# 687281_099_3.net
KiCad netlist of a schematic drawn in Altium Designer
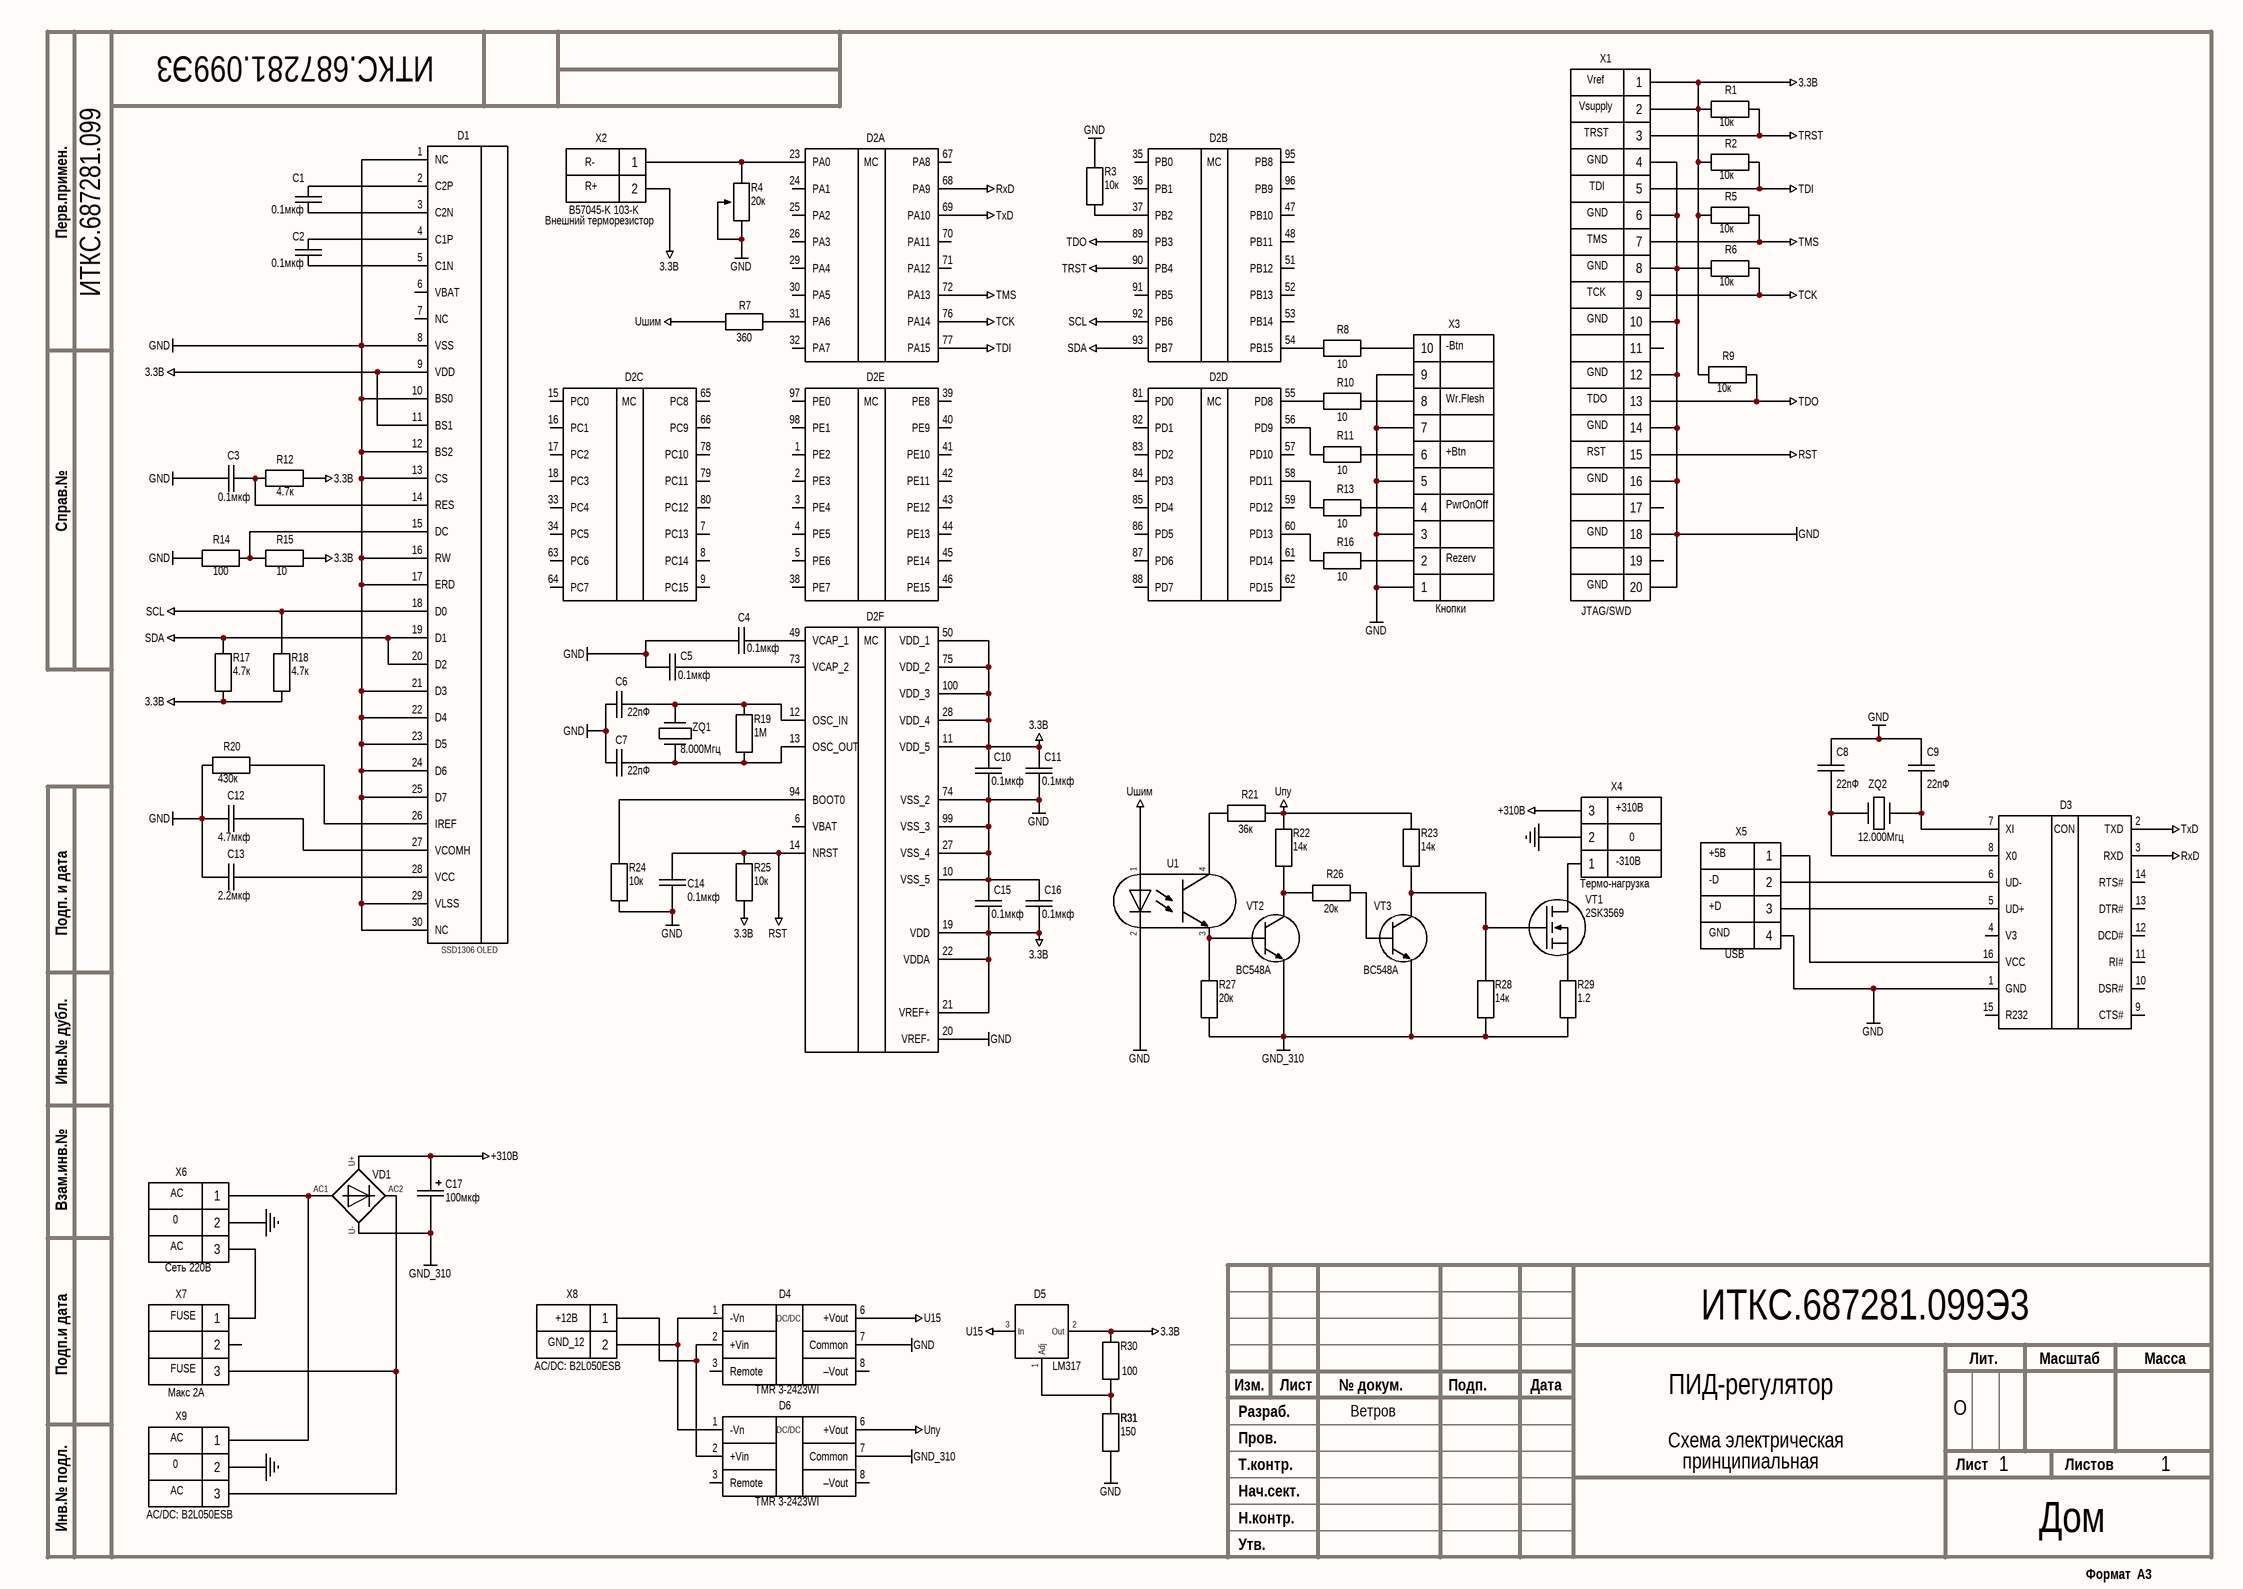
[diagram p0: ИТКС.687281.099Э3.SchDoc]

(export (version "E")
  (design (tool "Eeschema 10.0.6"))
  (components
    (comp (ref "C1")
      (value "0.1мкф")
      (footprint "C 0805")
      (description "0.1 мкФ X7R 50В 10% 0805, GRM21BR71H104KA01L")
      (libsource (lib "Passiv") (part "GRM21BR71H 104"))
    )
    (comp (ref "C2")
      (value "0.1мкф")
      (footprint "C 0805")
      (description "0.1 мкФ X7R 50В 10% 0805, GRM21BR71H104KA01L")
      (libsource (lib "Passiv") (part "GRM21BR71H 104"))
    )
    (comp (ref "C3")
      (value "0.1мкф")
      (footprint "C 0805")
      (description "0.1 мкФ X7R 50В 10% 0805, GRM21BR71H104KA01L")
      (libsource (lib "Passiv") (part "GRM21BR71H 104"))
    )
    (comp (ref "C4")
      (value "0.1мкф")
      (footprint "C 0805")
      (description "0.1 мкФ X7R 50В 10% 0805, GRM21BR71H104KA01L")
      (libsource (lib "Passiv") (part "GRM21BR71H 104"))
    )
    (comp (ref "C5")
      (value "0.1мкф")
      (footprint "C 0805")
      (description "0.1 мкФ X7R 50В 10% 0805, GRM21BR71H104KA01L")
      (libsource (lib "Passiv") (part "GRM21BR71H 104"))
    )
    (comp (ref "C6")
      (value "22пФ")
      (footprint "C 0805")
      (description "22пФ C0G 250B 5% 0805, GRM21A5C2E220J")
      (libsource (lib "Passiv") (part "GRM21A5C2E 220"))
    )
    (comp (ref "C7")
      (value "22пФ")
      (footprint "C 0805")
      (description "22пФ C0G 250B 5% 0805, GRM21A5C2E220J")
      (libsource (lib "Passiv") (part "GRM21A5C2E 220"))
    )
    (comp (ref "C8")
      (value "22пФ")
      (footprint "C 0805")
      (description "22пФ C0G 250B 5% 0805, GRM21A5C2E220J")
      (libsource (lib "Passiv") (part "GRM21A5C2E 220"))
    )
    (comp (ref "C9")
      (value "22пФ")
      (footprint "C 0805")
      (description "22пФ C0G 250B 5% 0805, GRM21A5C2E220J")
      (libsource (lib "Passiv") (part "GRM21A5C2E 220"))
    )
    (comp (ref "C10")
      (value "0.1мкф")
      (footprint "C 0805")
      (description "0.1 мкФ X7R 50В 10% 0805, GRM21BR71H104KA01L")
      (libsource (lib "Passiv") (part "GRM21BR71H 104"))
    )
    (comp (ref "C11")
      (value "0.1мкф")
      (footprint "C 0805")
      (description "0.1 мкФ X7R 50В 10% 0805, GRM21BR71H104KA01L")
      (libsource (lib "Passiv") (part "GRM21BR71H 104"))
    )
    (comp (ref "C12")
      (value "4.7мкф")
      (footprint "C 0805")
      (libsource (lib "Passiv") (part "GRM21BR61A 475"))
    )
    (comp (ref "C13")
      (value "2.2мкф")
      (footprint "C 1210")
      (description "2.2 мкФ X7R 10% 100В 1210, GRM32ER72A225K")
      (libsource (lib "Passiv") (part "GRM32ER72A 225"))
    )
    (comp (ref "C14")
      (value "0.1мкф")
      (footprint "C 0805")
      (description "0.1 мкФ X7R 50В 10% 0805, GRM21BR71H104KA01L")
      (libsource (lib "Passiv") (part "GRM21BR71H 104"))
    )
    (comp (ref "C15")
      (value "0.1мкф")
      (footprint "C 0805")
      (description "0.1 мкФ X7R 50В 10% 0805, GRM21BR71H104KA01L")
      (libsource (lib "Passiv") (part "GRM21BR71H 104"))
    )
    (comp (ref "C16")
      (value "0.1мкф")
      (footprint "C 0805")
      (description "0.1 мкФ X7R 50В 10% 0805, GRM21BR71H104KA01L")
      (libsource (lib "Passiv") (part "GRM21BR71H 104"))
    )
    (comp (ref "C17")
      (value "100мкф")
      (footprint "KSE-100")
      (description "Конденсатор электролитический KSE-100UF-400V-1830-105")
      (libsource (lib "Passiv") (part "KSE-100UF-400V-1830-105"))
    )
    (comp (ref "D1")
      (value "SSD1306 OLED")
      (footprint "50A-40BX")
      (libsource (lib "LCD") (part "SSD1306 OLED"))
    )
    (comp (ref "D2")
      (value "0")
      (footprint "LQFP - 100")
      (description "STM32F407VE6, Cortex-M3, 512k")
      (libsource (lib "") (part "STM32F407VE6_1"))
    )
    (comp (ref "D3")
      (value "CH340G")
      (footprint "SO16")
      (description "CH340G, Преобразователь интерфейса USB в UART [SOP-16]")
      (libsource (lib "CH") (part "CH340G"))
    )
    (comp (ref "D4")
      (value "TMR 3-2423WI")
      (footprint "TMR 3WI Series")
      (libsource (lib "Traco") (part "TMR 3-2423WI"))
    )
    (comp (ref "D5")
      (value "LM317")
      (footprint "TO-220")
      (description "LM317, Стабилизатор напряжения, линейный,регулируемый, 1,5А, TO220")
      (libsource (lib "LM") (part "LM317"))
    )
    (comp (ref "D6")
      (value "TMR 3-2423WI")
      (footprint "TMR 3WI Series")
      (libsource (lib "Traco") (part "TMR 3-2423WI"))
    )
    (comp (ref "R1")
      (value "10к")
      (footprint "R 0805")
      (description "0.125Вт 0805 10 кОм, 0п.1%, RT0805BRD0710KL")
      (libsource (lib "Passiv") (part "RT0805BRD07 10K"))
    )
    (comp (ref "R2")
      (value "10к")
      (footprint "R 0805")
      (description "0.125Вт 0805 10 кОм, 0п.1%, RT0805BRD0710KL")
      (libsource (lib "Passiv") (part "RT0805BRD07 10K"))
    )
    (comp (ref "R3")
      (value "10к")
      (footprint "R 0805")
      (description "0.125Вт 0805 10 кОм, 0п.1%, RT0805BRD0710KL")
      (libsource (lib "Passiv") (part "RT0805BRD07 10K"))
    )
    (comp (ref "R4")
      (value "20к")
      (footprint "JBR-3266W")
      (description "JBR-3266W-203-R, 20 кОм, Резистор подстроечный")
      (libsource (lib "Passiv") (part "JBR-3266W 203"))
    )
    (comp (ref "R5")
      (value "10к")
      (footprint "R 0805")
      (description "0.125Вт 0805 10 кОм, 0п.1%, RT0805BRD0710KL")
      (libsource (lib "Passiv") (part "RT0805BRD07 10K"))
    )
    (comp (ref "R6")
      (value "10к")
      (footprint "R 0805")
      (description "0.125Вт 0805 10 кОм, 0п.1%, RT0805BRD0710KL")
      (libsource (lib "Passiv") (part "RT0805BRD07 10K"))
    )
    (comp (ref "R7")
      (value "360")
      (footprint "R 0805")
      (description "RC0805FR-07360RL, (чип 0805 360 1%), Толстопленочный ЧИП-резистор 0805 360Ом +1% 0.125Вт")
      (libsource (lib "Passiv") (part "RC0805FR-07 360R"))
    )
    (comp (ref "R8")
      (value "10")
      (footprint "R 0805")
      (description "0.125Вт 0805 10 Ом, 1%, RC0805FR-0710RL")
      (libsource (lib "Passiv") (part "RC0805FR-07 10R"))
    )
    (comp (ref "R9")
      (value "10к")
      (footprint "R 0805")
      (description "0.125Вт 0805 10 кОм, 0п.1%, RT0805BRD0710KL")
      (libsource (lib "Passiv") (part "RT0805BRD07 10K"))
    )
    (comp (ref "R10")
      (value "10")
      (footprint "R 0805")
      (description "0.125Вт 0805 10 Ом, 1%, RC0805FR-0710RL")
      (libsource (lib "Passiv") (part "RC0805FR-07 10R"))
    )
    (comp (ref "R11")
      (value "10")
      (footprint "R 0805")
      (description "0.125Вт 0805 10 Ом, 1%, RC0805FR-0710RL")
      (libsource (lib "Passiv") (part "RC0805FR-07 10R"))
    )
    (comp (ref "R12")
      (value "4.7к")
      (footprint "R 0805")
      (description "0.125Вт 0805 4.7 кОм, 1%, RC0805FR-074K7L")
      (libsource (lib "Passiv") (part "RC0805FR07 4K7"))
    )
    (comp (ref "R13")
      (value "10")
      (footprint "R 0805")
      (description "0.125Вт 0805 10 Ом, 1%, RC0805FR-0710RL")
      (libsource (lib "Passiv") (part "RC0805FR-07 10R"))
    )
    (comp (ref "R14")
      (value "100")
      (footprint "R 0805")
      (description "0.125Вт 0805 100 Ом, 1%, RC0805FR-07100RL")
      (libsource (lib "Passiv") (part "RC0805FR-07 100R"))
    )
    (comp (ref "R15")
      (value "10")
      (footprint "R 0805")
      (description "0.125Вт 0805 10 Ом, 1%, RC0805FR-0710RL")
      (libsource (lib "") (part "RC0805FR-07 10R_1"))
    )
    (comp (ref "R16")
      (value "10")
      (footprint "R 0805")
      (description "0.125Вт 0805 10 Ом, 1%, RC0805FR-0710RL")
      (libsource (lib "Passiv") (part "RC0805FR-07 10R"))
    )
    (comp (ref "R17")
      (value "4.7к")
      (footprint "R 0805")
      (description "0.125Вт 0805 4.7 кОм, 1%, RC0805FR-074K7L")
      (libsource (lib "Passiv") (part "RC0805FR07 4K7"))
    )
    (comp (ref "R18")
      (value "4.7к")
      (footprint "R 0805")
      (description "0.125Вт 0805 4.7 кОм, 1%, RC0805FR-074K7L")
      (libsource (lib "Passiv") (part "RC0805FR07 4K7"))
    )
    (comp (ref "R19")
      (value "1М")
      (footprint "R 0805")
      (description "0.125Вт 0805 1 МОм, 1%, RC0805FR-071ML")
      (libsource (lib "Passiv") (part "RC0805FR-07 1M"))
    )
    (comp (ref "R20")
      (value "430к")
      (footprint "R 0805")
      (description "0.125Вт 0805 430 кОм, 5%, RC0805JR-07430KL")
      (libsource (lib "Passiv") (part "RC0805JR-07 430K"))
    )
    (comp (ref "R21")
      (value "36к")
      (footprint "R 0805")
      (description "RC0805FR-0736KL, (чип 0805 36.0К 1%), Толстопленочный ЧИП-резистор 0805 36кОм")
      (libsource (lib "Passiv") (part "RC0805FR-07 36K"))
    )
    (comp (ref "R22")
      (value "14к")
      (footprint "R 0805")
      (description "14 кОм 0805 1% RC0805FR-0714K")
      (libsource (lib "Passiv") (part "RC0805FR-07 14K"))
    )
    (comp (ref "R23")
      (value "14к")
      (footprint "R 0805")
      (description "14 кОм 0805 1% RC0805FR-0714K")
      (libsource (lib "Passiv") (part "RC0805FR-07 14K"))
    )
    (comp (ref "R24")
      (value "10к")
      (footprint "R 0805")
      (description "0.125Вт 0805 10 кОм, 0п.1%, RT0805BRD0710KL")
      (libsource (lib "Passiv") (part "RT0805BRD07 10K"))
    )
    (comp (ref "R25")
      (value "10к")
      (footprint "R 0805")
      (description "0.125Вт 0805 10 кОм, 0п.1%, RT0805BRD0710KL")
      (libsource (lib "Passiv") (part "RT0805BRD07 10K"))
    )
    (comp (ref "R26")
      (value "20к")
      (footprint "R 0805")
      (description "0.125Вт 0805 20 кОм, 1%, RC0805FR-0720KL")
      (libsource (lib "") (part "RC0805FR-07 20K_1"))
    )
    (comp (ref "R27")
      (value "20к")
      (footprint "R 0805")
      (description "0.125Вт 0805 20 кОм, 1%, RC0805FR-0720KL")
      (libsource (lib "Passiv") (part "RC0805FR-07 20K"))
    )
    (comp (ref "R28")
      (value "14к")
      (footprint "R 0805")
      (description "14 кОм 0805 1% RC0805FR-0714K")
      (libsource (lib "Passiv") (part "RC0805FR-07 14K"))
    )
    (comp (ref "R29")
      (value "1.2")
      (footprint "RX27-1")
      (description "RX27-1 1.2 Ом 5W 5% / SQP5, Мощный постоянный резистор , керамо-цементный корпус")
      (libsource (lib "Passiv") (part "RX27-1 1.2R"))
    )
    (comp (ref "R30")
      (value "100")
      (footprint "R 0805")
      (description "0.125Вт 0805 100 Ом, 1%, RC0805FR-07100RL")
      (libsource (lib "Passiv") (part "RC0805FR-07 100R"))
    )
    (comp (ref "R31")
      (value "150")
      (footprint "R 0805")
      (description "RC0805FR-07150RL, (чип 0805 150 1%), Толстопленочный ЧИП-резистор 0805 150Ом +1% 0.125Вт")
      (libsource (lib "Passiv") (part "RC0805FR-07 150R"))
    )
    (comp (ref "U1")
      (value "SFH618A-4X")
      (footprint "DIP4")
      (description "SFH618A-4X, Оптопара транзисторная [DIP-4]")
      (libsource (lib "Optic") (part "SFH618A-4X"))
    )
    (comp (ref "VD1")
      (value "0")
      (footprint "BR-10")
      (description "BR1001, Диодный мост однофазный 10А 100В [BR-10.] (=KBPC1001, BR101)")
      (libsource (lib "Passiv") (part "BR1001"))
    )
    (comp (ref "VT1")
      (value "2SK3569")
      (footprint "TO-220")
      (description "2SK3569, Транзистор, TT-MOSVI, N-канал, 600В, 10А")
      (libsource (lib "MOSFET") (part "2SK3569"))
    )
    (comp (ref "VT2")
      (value "BC548A")
      (footprint "TO-92")
      (description "BC548A, Транзистор NPN 30В 0.1А")
      (libsource (lib "Activ") (part "BC548A"))
    )
    (comp (ref "VT3")
      (value "BC548A")
      (footprint "TO-92")
      (description "BC548A, Транзистор NPN 30В 0.1А")
      (libsource (lib "Activ") (part "BC548A"))
    )
    (comp (ref "X1")
      (value "JTAG/SWD")
      (footprint "BH-20R (DS1013-20R) (IDC-20MR)")
      (description "BH-20R (DS1013-20R) (IDC-20MR), Вилка на плату угловая 20pin 2.54мм")
      (libsource (lib "Connectors") (part "BH-20R"))
    )
    (comp (ref "X2")
      (value "B57045-K 103-K")
      (footprint "PLS-2")
      (description "PLS-2 (DS-1021-1x2), Вилка штыревая 2.54мм 1x2pin прямая тип1")
      (libsource (lib "Connectors") (part "PLS-2"))
    )
    (comp (ref "X3")
      (value "Кнопки")
      (footprint "PLS-10")
      (description "PLS-10(DS-1021-1x10), Вилка штыревая 2.54мм 1x10pin прямая тип1")
      (libsource (lib "Connectors") (part "PLS-10"))
    )
    (comp (ref "X4")
      (value "Термо-нагрузка")
      (footprint "1-1123723-3")
      (description "1-1123723-3 (B3P-VH), Разъем 3 pin шаг 3.96мм")
      (libsource (lib "Connectors") (part "1-1123723-3"))
    )
    (comp (ref "X5")
      (value "USB")
      (footprint "PLS-4")
      (description "PLS-4 (DS-1021-1x4), Вилка штыревая 2.54мм 1x4pin прямая тип1")
      (libsource (lib "Connectors") (part "PLS-4"))
    )
    (comp (ref "X6")
      (value "Сеть 220В")
      (footprint "1-1123723-3")
      (description "1-1123723-3 (B3P-VH), Разъем 3 pin шаг 3.96мм")
      (libsource (lib "Connectors") (part "1-1123723-3"))
    )
    (comp (ref "X7")
      (value "Макс 2А")
      (footprint "1-1123723-3")
      (description "1-1123723-3 (B3P-VH), Разъем 3 pin шаг 3.96мм")
      (libsource (lib "Connectors") (part "1-1123723-3"))
    )
    (comp (ref "X8")
      (value "AC/DC: B2L050ESB")
      (footprint "PLS-2")
      (description "PLS-2 (DS-1021-1x2), Вилка штыревая 2.54мм 1x2pin прямая тип1")
      (libsource (lib "Connectors") (part "PLS-2"))
    )
    (comp (ref "X9")
      (value "AC/DC: B2L050ESB")
      (footprint "1-1123723-3")
      (description "1-1123723-3 (B3P-VH), Разъем 3 pin шаг 3.96мм")
      (libsource (lib "Connectors") (part "1-1123723-3"))
    )
    (comp (ref "ZQ1")
      (value "8.000Мгц")
      (footprint "HC-49S")
      (description "8.000Мгц, HC-49S, Кварцевый резонатор")
      (libsource (lib "Passiv") (part "HC-49S 8M"))
    )
    (comp (ref "ZQ2")
      (value "12.000Мгц")
      (footprint "HC-49S")
      (description "12.000Мгц, HC-49S, Кварцевый резонатор")
      (libsource (lib "Passiv") (part "HC-49S 12M"))
    )
  )
  (nets
    (net (code "1") (name "+310В") (class "Default")
      (node (ref "C17") (pin "1") (pinfunction "1_1") (pintype "passive"))
      (node (ref "VD1") (pin "U+") (pinfunction "U+_U+") (pintype "passive"))
      (node (ref "X4") (pin "3") (pinfunction "3_3") (pintype "passive"))
    )
    (net (code "2") (name "3.3В") (class "Default")
      (node (ref "C10") (pin "1") (pinfunction "1_1") (pintype "passive"))
      (node (ref "C11") (pin "1") (pinfunction "1_1") (pintype "passive"))
      (node (ref "C15") (pin "2") (pinfunction "2_2") (pintype "passive"))
      (node (ref "C16") (pin "2") (pinfunction "2_2") (pintype "passive"))
      (node (ref "D1") (pin "11") (pinfunction "BS1_11") (pintype "passive"))
      (node (ref "D1") (pin "9") (pinfunction "VDD_9") (pintype "passive"))
      (node (ref "D2") (pin "100") (pinfunction "VDD_3_100") (pintype "passive"))
      (node (ref "D2") (pin "11") (pinfunction "VDD_5_11") (pintype "passive"))
      (node (ref "D2") (pin "19") (pinfunction "VDD_19") (pintype "passive"))
      (node (ref "D2") (pin "21") (pinfunction "VREF+_21") (pintype "passive"))
      (node (ref "D2") (pin "22") (pinfunction "VDDA_22") (pintype "passive"))
      (node (ref "D2") (pin "28") (pinfunction "VDD_4_28") (pintype "passive"))
      (node (ref "D2") (pin "50") (pinfunction "VDD_1_50") (pintype "passive"))
      (node (ref "D2") (pin "75") (pinfunction "VDD_2_75") (pintype "passive"))
      (node (ref "D5") (pin "2") (pinfunction "Out_2") (pintype "passive"))
      (node (ref "R1") (pin "1") (pinfunction "1_1") (pintype "passive"))
      (node (ref "R12") (pin "2") (pinfunction "2_2") (pintype "passive"))
      (node (ref "R15") (pin "2") (pinfunction "2_2") (pintype "passive"))
      (node (ref "R17") (pin "1") (pinfunction "1_1") (pintype "passive"))
      (node (ref "R18") (pin "1") (pinfunction "1_1") (pintype "passive"))
      (node (ref "R2") (pin "1") (pinfunction "1_1") (pintype "passive"))
      (node (ref "R25") (pin "1") (pinfunction "1_1") (pintype "passive"))
      (node (ref "R30") (pin "2") (pinfunction "2_2") (pintype "passive"))
      (node (ref "R5") (pin "1") (pinfunction "1_1") (pintype "passive"))
      (node (ref "R9") (pin "1") (pinfunction "1_1") (pintype "passive"))
      (node (ref "X1") (pin "1") (pinfunction "1_1") (pintype "passive"))
      (node (ref "X1") (pin "2") (pinfunction "2_2") (pintype "passive"))
      (node (ref "X2") (pin "2") (pinfunction "2_2") (pintype "passive"))
    )
    (net (code "3") (name "GND") (class "Default")
      (node (ref "C10") (pin "2") (pinfunction "2_2") (pintype "passive"))
      (node (ref "C11") (pin "2") (pinfunction "2_2") (pintype "passive"))
      (node (ref "C12") (pin "1") (pinfunction "1_1") (pintype "passive"))
      (node (ref "C13") (pin "1") (pinfunction "1_1") (pintype "passive"))
      (node (ref "C14") (pin "2") (pinfunction "2_2") (pintype "passive"))
      (node (ref "C15") (pin "1") (pinfunction "1_1") (pintype "passive"))
      (node (ref "C16") (pin "1") (pinfunction "1_1") (pintype "passive"))
      (node (ref "C3") (pin "2") (pinfunction "2_2") (pintype "passive"))
      (node (ref "C4") (pin "2") (pinfunction "2_2") (pintype "passive"))
      (node (ref "C5") (pin "2") (pinfunction "2_2") (pintype "passive"))
      (node (ref "C6") (pin "1") (pinfunction "1_1") (pintype "passive"))
      (node (ref "C7") (pin "1") (pinfunction "1_1") (pintype "passive"))
      (node (ref "C8") (pin "2") (pinfunction "2_2") (pintype "passive"))
      (node (ref "C9") (pin "2") (pinfunction "2_2") (pintype "passive"))
      (node (ref "D1") (pin "1") (pinfunction "NC_1") (pintype "passive"))
      (node (ref "D1") (pin "10") (pinfunction "BS0_10") (pintype "passive"))
      (node (ref "D1") (pin "12") (pinfunction "BS2_12") (pintype "passive"))
      (node (ref "D1") (pin "13") (pinfunction "CS_13") (pintype "passive"))
      (node (ref "D1") (pin "16") (pinfunction "RW_16") (pintype "passive"))
      (node (ref "D1") (pin "17") (pinfunction "ERD_17") (pintype "passive"))
      (node (ref "D1") (pin "21") (pinfunction "D3_21") (pintype "passive"))
      (node (ref "D1") (pin "22") (pinfunction "D4_22") (pintype "passive"))
      (node (ref "D1") (pin "23") (pinfunction "D5_23") (pintype "passive"))
      (node (ref "D1") (pin "24") (pinfunction "D6_24") (pintype "passive"))
      (node (ref "D1") (pin "25") (pinfunction "D7_25") (pintype "passive"))
      (node (ref "D1") (pin "29") (pinfunction "VLSS_29") (pintype "passive"))
      (node (ref "D1") (pin "30") (pinfunction "NC_30") (pintype "passive"))
      (node (ref "D1") (pin "8") (pinfunction "VSS_8") (pintype "passive"))
      (node (ref "D2") (pin "10") (pinfunction "VSS_5_10") (pintype "passive"))
      (node (ref "D2") (pin "20") (pinfunction "VREF-_20") (pintype "passive"))
      (node (ref "D2") (pin "27") (pinfunction "VSS_4_27") (pintype "passive"))
      (node (ref "D2") (pin "74") (pinfunction "VSS_2_74") (pintype "passive"))
      (node (ref "D2") (pin "99") (pinfunction "VSS_3_99") (pintype "passive"))
      (node (ref "D3") (pin "1") (pinfunction "GND_1") (pintype "passive"))
      (node (ref "D4") (pin "7") (pinfunction "Common_7") (pintype "passive"))
      (node (ref "R14") (pin "1") (pinfunction "1_1") (pintype "passive"))
      (node (ref "R20") (pin "1") (pinfunction "1_1") (pintype "passive"))
      (node (ref "R24") (pin "1") (pinfunction "1_1") (pintype "passive"))
      (node (ref "R3") (pin "2") (pinfunction "2_2") (pintype "passive"))
      (node (ref "R31") (pin "1") (pinfunction "1_1") (pintype "passive"))
      (node (ref "R4") (pin "1") (pinfunction "1_1") (pintype "passive"))
      (node (ref "R4") (pin "3") (pinfunction "3_3") (pintype "passive"))
      (node (ref "R6") (pin "1") (pinfunction "1_1") (pintype "passive"))
      (node (ref "U1") (pin "2") (pinfunction "C_2") (pintype "passive"))
      (node (ref "X1") (pin "10") (pinfunction "10_10") (pintype "passive"))
      (node (ref "X1") (pin "12") (pinfunction "12_12") (pintype "passive"))
      (node (ref "X1") (pin "14") (pinfunction "14_14") (pintype "passive"))
      (node (ref "X1") (pin "16") (pinfunction "16_16") (pintype "passive"))
      (node (ref "X1") (pin "18") (pinfunction "18_18") (pintype "passive"))
      (node (ref "X1") (pin "20") (pinfunction "20_20") (pintype "passive"))
      (node (ref "X1") (pin "4") (pinfunction "4_4") (pintype "passive"))
      (node (ref "X1") (pin "6") (pinfunction "6_6") (pintype "passive"))
      (node (ref "X1") (pin "8") (pinfunction "8_8") (pintype "passive"))
      (node (ref "X3") (pin "1") (pinfunction "1_1") (pintype "passive"))
      (node (ref "X3") (pin "3") (pinfunction "3_3") (pintype "passive"))
      (node (ref "X3") (pin "5") (pinfunction "5_5") (pintype "passive"))
      (node (ref "X3") (pin "7") (pinfunction "7_7") (pintype "passive"))
      (node (ref "X3") (pin "9") (pinfunction "9_9") (pintype "passive"))
      (node (ref "X5") (pin "4") (pinfunction "4_4") (pintype "passive"))
    )
    (net (code "4") (name "GND_310") (class "Default")
      (node (ref "C17") (pin "2") (pinfunction "2_2") (pintype "passive"))
      (node (ref "D6") (pin "7") (pinfunction "Common_7") (pintype "passive"))
      (node (ref "R27") (pin "1") (pinfunction "1_1") (pintype "passive"))
      (node (ref "R28") (pin "1") (pinfunction "1_1") (pintype "passive"))
      (node (ref "R29") (pin "1") (pinfunction "1_1") (pintype "passive"))
      (node (ref "VD1") (pin "U-") (pinfunction "U-_U-") (pintype "passive"))
      (node (ref "VT2") (pin "E") (pinfunction "E_E") (pintype "passive"))
      (node (ref "VT3") (pin "E") (pinfunction "E_E") (pintype "passive"))
    )
    (net (code "5") (name "GND_set") (class "Default")
      (node (ref "X4") (pin "2") (pinfunction "2_2") (pintype "passive"))
      (node (ref "X6") (pin "2") (pinfunction "2_2") (pintype "passive"))
      (node (ref "X9") (pin "2") (pinfunction "2_2") (pintype "passive"))
    )
    (net (code "6") (name "Net-(D1-C1N)") (class "Default")
      (node (ref "C2") (pin "1") (pinfunction "1_1") (pintype "passive"))
      (node (ref "D1") (pin "5") (pinfunction "C1N_5") (pintype "passive"))
    )
    (net (code "7") (name "Net-(D1-C1P)") (class "Default")
      (node (ref "C2") (pin "2") (pinfunction "2_2") (pintype "passive"))
      (node (ref "D1") (pin "4") (pinfunction "C1P_4") (pintype "passive"))
    )
    (net (code "8") (name "Net-(D1-C2N)") (class "Default")
      (node (ref "C1") (pin "1") (pinfunction "1_1") (pintype "passive"))
      (node (ref "D1") (pin "3") (pinfunction "C2N_3") (pintype "passive"))
    )
    (net (code "9") (name "Net-(D1-C2P)") (class "Default")
      (node (ref "C1") (pin "2") (pinfunction "2_2") (pintype "passive"))
      (node (ref "D1") (pin "2") (pinfunction "C2P_2") (pintype "passive"))
    )
    (net (code "10") (name "Net-(D1-DC)") (class "Default")
      (node (ref "D1") (pin "15") (pinfunction "DC_15") (pintype "passive"))
      (node (ref "R14") (pin "2") (pinfunction "2_2") (pintype "passive"))
      (node (ref "R15") (pin "1") (pinfunction "1_1") (pintype "passive"))
    )
    (net (code "11") (name "Net-(D1-IREF)") (class "Default")
      (node (ref "D1") (pin "26") (pinfunction "IREF_26") (pintype "passive"))
      (node (ref "R20") (pin "2") (pinfunction "2_2") (pintype "passive"))
    )
    (net (code "12") (name "Net-(D1-RES)") (class "Default")
      (node (ref "C3") (pin "1") (pinfunction "1_1") (pintype "passive"))
      (node (ref "D1") (pin "14") (pinfunction "RES_14") (pintype "passive"))
      (node (ref "R12") (pin "1") (pinfunction "1_1") (pintype "passive"))
    )
    (net (code "13") (name "Net-(D1-VCC)") (class "Default")
      (node (ref "C13") (pin "2") (pinfunction "2_2") (pintype "passive"))
      (node (ref "D1") (pin "28") (pinfunction "VCC_28") (pintype "passive"))
    )
    (net (code "14") (name "Net-(D1-VCOMH)") (class "Default")
      (node (ref "C12") (pin "2") (pinfunction "2_2") (pintype "passive"))
      (node (ref "D1") (pin "27") (pinfunction "VCOMH_27") (pintype "passive"))
    )
    (net (code "15") (name "Net-(D2A-PA0)") (class "Default")
      (node (ref "D2") (pin "23") (pinfunction "PA0_23") (pintype "passive"))
      (node (ref "R4") (pin "2") (pinfunction "2_2") (pintype "passive"))
      (node (ref "X2") (pin "1") (pinfunction "1_1") (pintype "passive"))
    )
    (net (code "16") (name "Net-(D2A-PA6)") (class "Default")
      (node (ref "D2") (pin "31") (pinfunction "PA6_31") (pintype "passive"))
      (node (ref "R7") (pin "1") (pinfunction "1_1") (pintype "passive"))
    )
    (net (code "17") (name "Net-(D2B-PB2)") (class "Default")
      (node (ref "D2") (pin "37") (pinfunction "PB2_37") (pintype "passive"))
      (node (ref "R3") (pin "1") (pinfunction "1_1") (pintype "passive"))
    )
    (net (code "18") (name "Net-(D2B-PB15)") (class "Default")
      (node (ref "D2") (pin "54") (pinfunction "PB15_54") (pintype "passive"))
      (node (ref "R8") (pin "1") (pinfunction "1_1") (pintype "passive"))
    )
    (net (code "19") (name "Net-(D2D-PD8)") (class "Default")
      (node (ref "D2") (pin "55") (pinfunction "PD8_55") (pintype "passive"))
      (node (ref "R10") (pin "1") (pinfunction "1_1") (pintype "passive"))
    )
    (net (code "20") (name "Net-(D2D-PD9)") (class "Default")
      (node (ref "D2") (pin "56") (pinfunction "PD9_56") (pintype "passive"))
      (node (ref "R11") (pin "1") (pinfunction "1_1") (pintype "passive"))
    )
    (net (code "21") (name "Net-(D2D-PD11)") (class "Default")
      (node (ref "D2") (pin "58") (pinfunction "PD11_58") (pintype "passive"))
      (node (ref "R13") (pin "1") (pinfunction "1_1") (pintype "passive"))
    )
    (net (code "22") (name "Net-(D2D-PD13)") (class "Default")
      (node (ref "D2") (pin "60") (pinfunction "PD13_60") (pintype "passive"))
      (node (ref "R16") (pin "1") (pinfunction "1_1") (pintype "passive"))
    )
    (net (code "23") (name "Net-(D2F-BOOT0)") (class "Default")
      (node (ref "D2") (pin "94") (pinfunction "BOOT0_94") (pintype "passive"))
      (node (ref "R24") (pin "2") (pinfunction "2_2") (pintype "passive"))
    )
    (net (code "24") (name "Net-(D2F-OSC_IN)") (class "Default")
      (node (ref "C6") (pin "2") (pinfunction "2_2") (pintype "passive"))
      (node (ref "D2") (pin "12") (pinfunction "OSC_IN_12") (pintype "passive"))
      (node (ref "R19") (pin "2") (pinfunction "2_2") (pintype "passive"))
      (node (ref "ZQ1") (pin "2") (pinfunction "2_2") (pintype "passive"))
    )
    (net (code "25") (name "Net-(D2F-OSC_OUT)") (class "Default")
      (node (ref "C7") (pin "2") (pinfunction "2_2") (pintype "passive"))
      (node (ref "D2") (pin "13") (pinfunction "OSC_OUT_13") (pintype "passive"))
      (node (ref "R19") (pin "1") (pinfunction "1_1") (pintype "passive"))
      (node (ref "ZQ1") (pin "1") (pinfunction "1_1") (pintype "passive"))
    )
    (net (code "26") (name "Net-(D2F-VCAP_1)") (class "Default")
      (node (ref "C4") (pin "1") (pinfunction "1_1") (pintype "passive"))
      (node (ref "D2") (pin "49") (pinfunction "VCAP_1_49") (pintype "passive"))
    )
    (net (code "27") (name "Net-(D2F-VCAP_2)") (class "Default")
      (node (ref "C5") (pin "1") (pinfunction "1_1") (pintype "passive"))
      (node (ref "D2") (pin "73") (pinfunction "VCAP_2_73") (pintype "passive"))
    )
    (net (code "28") (name "Net-(D3-UD+)") (class "Default")
      (node (ref "D3") (pin "5") (pinfunction "UD+_5") (pintype "passive"))
      (node (ref "X5") (pin "3") (pinfunction "3_3") (pintype "passive"))
    )
    (net (code "29") (name "Net-(D3-UD-)") (class "Default")
      (node (ref "D3") (pin "6") (pinfunction "UD-_6") (pintype "passive"))
      (node (ref "X5") (pin "2") (pinfunction "2_2") (pintype "passive"))
    )
    (net (code "30") (name "Net-(D3-VCC)") (class "Default")
      (node (ref "D3") (pin "16") (pinfunction "VCC_16") (pintype "passive"))
      (node (ref "X5") (pin "1") (pinfunction "1_1") (pintype "passive"))
    )
    (net (code "31") (name "Net-(D3-X0)") (class "Default")
      (node (ref "C8") (pin "1") (pinfunction "1_1") (pintype "passive"))
      (node (ref "D3") (pin "8") (pinfunction "X0_8") (pintype "passive"))
      (node (ref "ZQ2") (pin "1") (pinfunction "1_1") (pintype "passive"))
    )
    (net (code "32") (name "Net-(D3-XI)") (class "Default")
      (node (ref "C9") (pin "1") (pinfunction "1_1") (pintype "passive"))
      (node (ref "D3") (pin "7") (pinfunction "XI_7") (pintype "passive"))
      (node (ref "ZQ2") (pin "2") (pinfunction "2_2") (pintype "passive"))
    )
    (net (code "33") (name "Net-(D4-+Vin)") (class "Default")
      (node (ref "D4") (pin "2") (pinfunction "+Vin_2") (pintype "passive"))
      (node (ref "D6") (pin "2") (pinfunction "+Vin_2") (pintype "passive"))
      (node (ref "X8") (pin "1") (pinfunction "1_1") (pintype "passive"))
    )
    (net (code "34") (name "Net-(D4--Vn)") (class "Default")
      (node (ref "D4") (pin "1") (pinfunction "-Vn_1") (pintype "passive"))
      (node (ref "D6") (pin "1") (pinfunction "-Vn_1") (pintype "passive"))
      (node (ref "X8") (pin "2") (pinfunction "2_2") (pintype "passive"))
    )
    (net (code "35") (name "Net-(D5-Adj)") (class "Default")
      (node (ref "D5") (pin "1") (pinfunction "Adj_1") (pintype "passive"))
      (node (ref "R30") (pin "1") (pinfunction "1_1") (pintype "passive"))
      (node (ref "R31") (pin "2") (pinfunction "2_2") (pintype "passive"))
    )
    (net (code "36") (name "Net-(R8-Pad2)") (class "Default")
      (node (ref "R8") (pin "2") (pinfunction "2_2") (pintype "passive"))
      (node (ref "X3") (pin "10") (pinfunction "10_10") (pintype "passive"))
    )
    (net (code "37") (name "Net-(R10-Pad2)") (class "Default")
      (node (ref "R10") (pin "2") (pinfunction "2_2") (pintype "passive"))
      (node (ref "X3") (pin "8") (pinfunction "8_8") (pintype "passive"))
    )
    (net (code "38") (name "Net-(R11-Pad2)") (class "Default")
      (node (ref "R11") (pin "2") (pinfunction "2_2") (pintype "passive"))
      (node (ref "X3") (pin "6") (pinfunction "6_6") (pintype "passive"))
    )
    (net (code "39") (name "Net-(R13-Pad2)") (class "Default")
      (node (ref "R13") (pin "2") (pinfunction "2_2") (pintype "passive"))
      (node (ref "X3") (pin "4") (pinfunction "4_4") (pintype "passive"))
    )
    (net (code "40") (name "Net-(R16-Pad2)") (class "Default")
      (node (ref "R16") (pin "2") (pinfunction "2_2") (pintype "passive"))
      (node (ref "X3") (pin "2") (pinfunction "2_2") (pintype "passive"))
    )
    (net (code "41") (name "Net-(R21-Pad1)") (class "Default")
      (node (ref "R21") (pin "1") (pinfunction "1_1") (pintype "passive"))
      (node (ref "U1") (pin "4") (pinfunction "C_4") (pintype "passive"))
    )
    (net (code "42") (name "Net-(R22-Pad1)") (class "Default")
      (node (ref "R22") (pin "1") (pinfunction "1_1") (pintype "passive"))
      (node (ref "R26") (pin "2") (pinfunction "2_2") (pintype "passive"))
      (node (ref "VT2") (pin "K") (pinfunction "K_K") (pintype "passive"))
    )
    (net (code "43") (name "Net-(R26-Pad1)") (class "Default")
      (node (ref "R26") (pin "1") (pinfunction "1_1") (pintype "passive"))
      (node (ref "VT3") (pin "B") (pinfunction "B_B") (pintype "passive"))
    )
    (net (code "44") (name "Net-(U1-E)") (class "Default")
      (node (ref "R27") (pin "2") (pinfunction "2_2") (pintype "passive"))
      (node (ref "U1") (pin "3") (pinfunction "E_3") (pintype "passive"))
      (node (ref "VT2") (pin "B") (pinfunction "B_B") (pintype "passive"))
    )
    (net (code "45") (name "Net-(VD1-PadAC1)") (class "Default")
      (node (ref "VD1") (pin "AC1") (pinfunction "AC1_AC1") (pintype "passive"))
      (node (ref "X6") (pin "1") (pinfunction "1_1") (pintype "passive"))
      (node (ref "X9") (pin "1") (pinfunction "1_1") (pintype "passive"))
    )
    (net (code "46") (name "Net-(VD1-PadAC2)") (class "Default")
      (node (ref "VD1") (pin "AC2") (pinfunction "AC2_AC2") (pintype "passive"))
      (node (ref "X7") (pin "3") (pinfunction "3_3") (pintype "passive"))
      (node (ref "X9") (pin "3") (pinfunction "3_3") (pintype "passive"))
    )
    (net (code "47") (name "Net-(VT1-Drain)") (class "Default")
      (node (ref "VT1") (pin "2") (pinfunction "Drain_2") (pintype "passive"))
      (node (ref "X4") (pin "1") (pinfunction "1_1") (pintype "passive"))
    )
    (net (code "48") (name "Net-(VT1-Gate)") (class "Default")
      (node (ref "R23") (pin "1") (pinfunction "1_1") (pintype "passive"))
      (node (ref "R28") (pin "2") (pinfunction "2_2") (pintype "passive"))
      (node (ref "VT1") (pin "1") (pinfunction "Gate_1") (pintype "passive"))
      (node (ref "VT3") (pin "K") (pinfunction "K_K") (pintype "passive"))
    )
    (net (code "49") (name "Net-(VT1-Source)") (class "Default")
      (node (ref "R29") (pin "2") (pinfunction "2_2") (pintype "passive"))
      (node (ref "VT1") (pin "3") (pinfunction "Source_3") (pintype "passive"))
    )
    (net (code "50") (name "Net-(X6-Pad3)") (class "Default")
      (node (ref "X6") (pin "3") (pinfunction "3_3") (pintype "passive"))
      (node (ref "X7") (pin "1") (pinfunction "1_1") (pintype "passive"))
    )
    (net (code "51") (name "RST") (class "Default")
      (node (ref "C14") (pin "1") (pinfunction "1_1") (pintype "passive"))
      (node (ref "D2") (pin "14") (pinfunction "NRST_14") (pintype "passive"))
      (node (ref "R25") (pin "2") (pinfunction "2_2") (pintype "passive"))
      (node (ref "X1") (pin "15") (pinfunction "15_15") (pintype "passive"))
    )
    (net (code "52") (name "RxD") (class "Default")
      (node (ref "D2") (pin "68") (pinfunction "PA9_68") (pintype "passive"))
      (node (ref "D3") (pin "3") (pinfunction "RXD_3") (pintype "passive"))
    )
    (net (code "53") (name "SCL") (class "Default")
      (node (ref "D1") (pin "18") (pinfunction "D0_18") (pintype "passive"))
      (node (ref "D2") (pin "92") (pinfunction "PB6_92") (pintype "passive"))
      (node (ref "R18") (pin "2") (pinfunction "2_2") (pintype "passive"))
    )
    (net (code "54") (name "SDA") (class "Default")
      (node (ref "D1") (pin "19") (pinfunction "D1_19") (pintype "passive"))
      (node (ref "D1") (pin "20") (pinfunction "D2_20") (pintype "passive"))
      (node (ref "D2") (pin "93") (pinfunction "PB7_93") (pintype "passive"))
      (node (ref "R17") (pin "2") (pinfunction "2_2") (pintype "passive"))
    )
    (net (code "55") (name "TCK") (class "Default")
      (node (ref "D2") (pin "76") (pinfunction "PA14_76") (pintype "passive"))
      (node (ref "R6") (pin "2") (pinfunction "2_2") (pintype "passive"))
      (node (ref "X1") (pin "9") (pinfunction "9_9") (pintype "passive"))
    )
    (net (code "56") (name "TDI") (class "Default")
      (node (ref "D2") (pin "77") (pinfunction "PA15_77") (pintype "passive"))
      (node (ref "R2") (pin "2") (pinfunction "2_2") (pintype "passive"))
      (node (ref "X1") (pin "5") (pinfunction "5_5") (pintype "passive"))
    )
    (net (code "57") (name "TDO") (class "Default")
      (node (ref "D2") (pin "89") (pinfunction "PB3_89") (pintype "passive"))
      (node (ref "R9") (pin "2") (pinfunction "2_2") (pintype "passive"))
      (node (ref "X1") (pin "13") (pinfunction "13_13") (pintype "passive"))
    )
    (net (code "58") (name "TMS") (class "Default")
      (node (ref "D2") (pin "72") (pinfunction "PA13_72") (pintype "passive"))
      (node (ref "R5") (pin "2") (pinfunction "2_2") (pintype "passive"))
      (node (ref "X1") (pin "7") (pinfunction "7_7") (pintype "passive"))
    )
    (net (code "59") (name "TRST") (class "Default")
      (node (ref "D2") (pin "90") (pinfunction "PB4_90") (pintype "passive"))
      (node (ref "R1") (pin "2") (pinfunction "2_2") (pintype "passive"))
      (node (ref "X1") (pin "3") (pinfunction "3_3") (pintype "passive"))
    )
    (net (code "60") (name "TxD") (class "Default")
      (node (ref "D2") (pin "69") (pinfunction "PA10_69") (pintype "passive"))
      (node (ref "D3") (pin "2") (pinfunction "TXD_2") (pintype "passive"))
    )
    (net (code "61") (name "U15") (class "Default")
      (node (ref "D4") (pin "6") (pinfunction "+Vout_6") (pintype "passive"))
      (node (ref "D5") (pin "3") (pinfunction "In_3") (pintype "passive"))
    )
    (net (code "62") (name "Uпу") (class "Default")
      (node (ref "D6") (pin "6") (pinfunction "+Vout_6") (pintype "passive"))
      (node (ref "R21") (pin "2") (pinfunction "2_2") (pintype "passive"))
      (node (ref "R22") (pin "2") (pinfunction "2_2") (pintype "passive"))
      (node (ref "R23") (pin "2") (pinfunction "2_2") (pintype "passive"))
    )
    (net (code "63") (name "Uшим") (class "Default")
      (node (ref "R7") (pin "2") (pinfunction "2_2") (pintype "passive"))
      (node (ref "U1") (pin "1") (pinfunction "A_1") (pintype "passive"))
    )
    (net (code "64") (name "unconnected-(D1-NC-Pad7)") (class "Default")
      (node (ref "D1") (pin "7") (pinfunction "NC_7") (pintype "passive"))
    )
    (net (code "65") (name "unconnected-(D1-VBAT-Pad6)") (class "Default")
      (node (ref "D1") (pin "6") (pinfunction "VBAT_6") (pintype "passive"))
    )
    (net (code "66") (name "unconnected-(D2A-PA1-Pad24)") (class "Default")
      (node (ref "D2") (pin "24") (pinfunction "PA1_24") (pintype "passive"))
    )
    (net (code "67") (name "unconnected-(D2A-PA2-Pad25)") (class "Default")
      (node (ref "D2") (pin "25") (pinfunction "PA2_25") (pintype "passive"))
    )
    (net (code "68") (name "unconnected-(D2A-PA3-Pad26)") (class "Default")
      (node (ref "D2") (pin "26") (pinfunction "PA3_26") (pintype "passive"))
    )
    (net (code "69") (name "unconnected-(D2A-PA4-Pad29)") (class "Default")
      (node (ref "D2") (pin "29") (pinfunction "PA4_29") (pintype "passive"))
    )
    (net (code "70") (name "unconnected-(D2A-PA5-Pad30)") (class "Default")
      (node (ref "D2") (pin "30") (pinfunction "PA5_30") (pintype "passive"))
    )
    (net (code "71") (name "unconnected-(D2A-PA7-Pad32)") (class "Default")
      (node (ref "D2") (pin "32") (pinfunction "PA7_32") (pintype "passive"))
    )
    (net (code "72") (name "unconnected-(D2A-PA8-Pad67)") (class "Default")
      (node (ref "D2") (pin "67") (pinfunction "PA8_67") (pintype "passive"))
    )
    (net (code "73") (name "unconnected-(D2A-PA11-Pad70)") (class "Default")
      (node (ref "D2") (pin "70") (pinfunction "PA11_70") (pintype "passive"))
    )
    (net (code "74") (name "unconnected-(D2A-PA12-Pad71)") (class "Default")
      (node (ref "D2") (pin "71") (pinfunction "PA12_71") (pintype "passive"))
    )
    (net (code "75") (name "unconnected-(D2B-PB0-Pad35)") (class "Default")
      (node (ref "D2") (pin "35") (pinfunction "PB0_35") (pintype "passive"))
    )
    (net (code "76") (name "unconnected-(D2B-PB1-Pad36)") (class "Default")
      (node (ref "D2") (pin "36") (pinfunction "PB1_36") (pintype "passive"))
    )
    (net (code "77") (name "unconnected-(D2B-PB5-Pad91)") (class "Default")
      (node (ref "D2") (pin "91") (pinfunction "PB5_91") (pintype "passive"))
    )
    (net (code "78") (name "unconnected-(D2B-PB8-Pad95)") (class "Default")
      (node (ref "D2") (pin "95") (pinfunction "PB8_95") (pintype "passive"))
    )
    (net (code "79") (name "unconnected-(D2B-PB9-Pad96)") (class "Default")
      (node (ref "D2") (pin "96") (pinfunction "PB9_96") (pintype "passive"))
    )
    (net (code "80") (name "unconnected-(D2B-PB10-Pad47)") (class "Default")
      (node (ref "D2") (pin "47") (pinfunction "PB10_47") (pintype "passive"))
    )
    (net (code "81") (name "unconnected-(D2B-PB11-Pad48)") (class "Default")
      (node (ref "D2") (pin "48") (pinfunction "PB11_48") (pintype "passive"))
    )
    (net (code "82") (name "unconnected-(D2B-PB12-Pad51)") (class "Default")
      (node (ref "D2") (pin "51") (pinfunction "PB12_51") (pintype "passive"))
    )
    (net (code "83") (name "unconnected-(D2B-PB13-Pad52)") (class "Default")
      (node (ref "D2") (pin "52") (pinfunction "PB13_52") (pintype "passive"))
    )
    (net (code "84") (name "unconnected-(D2B-PB14-Pad53)") (class "Default")
      (node (ref "D2") (pin "53") (pinfunction "PB14_53") (pintype "passive"))
    )
    (net (code "85") (name "unconnected-(D2C-PC0-Pad15)") (class "Default")
      (node (ref "D2") (pin "15") (pinfunction "PC0_15") (pintype "passive"))
    )
    (net (code "86") (name "unconnected-(D2C-PC1-Pad16)") (class "Default")
      (node (ref "D2") (pin "16") (pinfunction "PC1_16") (pintype "passive"))
    )
    (net (code "87") (name "unconnected-(D2C-PC2-Pad17)") (class "Default")
      (node (ref "D2") (pin "17") (pinfunction "PC2_17") (pintype "passive"))
    )
    (net (code "88") (name "unconnected-(D2C-PC3-Pad18)") (class "Default")
      (node (ref "D2") (pin "18") (pinfunction "PC3_18") (pintype "passive"))
    )
    (net (code "89") (name "unconnected-(D2C-PC4-Pad33)") (class "Default")
      (node (ref "D2") (pin "33") (pinfunction "PC4_33") (pintype "passive"))
    )
    (net (code "90") (name "unconnected-(D2C-PC5-Pad34)") (class "Default")
      (node (ref "D2") (pin "34") (pinfunction "PC5_34") (pintype "passive"))
    )
    (net (code "91") (name "unconnected-(D2C-PC6-Pad63)") (class "Default")
      (node (ref "D2") (pin "63") (pinfunction "PC6_63") (pintype "passive"))
    )
    (net (code "92") (name "unconnected-(D2C-PC7-Pad64)") (class "Default")
      (node (ref "D2") (pin "64") (pinfunction "PC7_64") (pintype "passive"))
    )
    (net (code "93") (name "unconnected-(D2C-PC8-Pad65)") (class "Default")
      (node (ref "D2") (pin "65") (pinfunction "PC8_65") (pintype "passive"))
    )
    (net (code "94") (name "unconnected-(D2C-PC9-Pad66)") (class "Default")
      (node (ref "D2") (pin "66") (pinfunction "PC9_66") (pintype "passive"))
    )
    (net (code "95") (name "unconnected-(D2C-PC10-Pad78)") (class "Default")
      (node (ref "D2") (pin "78") (pinfunction "PC10_78") (pintype "passive"))
    )
    (net (code "96") (name "unconnected-(D2C-PC11-Pad79)") (class "Default")
      (node (ref "D2") (pin "79") (pinfunction "PC11_79") (pintype "passive"))
    )
    (net (code "97") (name "unconnected-(D2C-PC12-Pad80)") (class "Default")
      (node (ref "D2") (pin "80") (pinfunction "PC12_80") (pintype "passive"))
    )
    (net (code "98") (name "unconnected-(D2C-PC13-Pad7)") (class "Default")
      (node (ref "D2") (pin "7") (pinfunction "PC13_7") (pintype "passive"))
    )
    (net (code "99") (name "unconnected-(D2C-PC14-Pad8)") (class "Default")
      (node (ref "D2") (pin "8") (pinfunction "PC14_8") (pintype "passive"))
    )
    (net (code "100") (name "unconnected-(D2C-PC15-Pad9)") (class "Default")
      (node (ref "D2") (pin "9") (pinfunction "PC15_9") (pintype "passive"))
    )
    (net (code "101") (name "unconnected-(D2D-PD0-Pad81)") (class "Default")
      (node (ref "D2") (pin "81") (pinfunction "PD0_81") (pintype "passive"))
    )
    (net (code "102") (name "unconnected-(D2D-PD1-Pad82)") (class "Default")
      (node (ref "D2") (pin "82") (pinfunction "PD1_82") (pintype "passive"))
    )
    (net (code "103") (name "unconnected-(D2D-PD2-Pad83)") (class "Default")
      (node (ref "D2") (pin "83") (pinfunction "PD2_83") (pintype "passive"))
    )
    (net (code "104") (name "unconnected-(D2D-PD3-Pad84)") (class "Default")
      (node (ref "D2") (pin "84") (pinfunction "PD3_84") (pintype "passive"))
    )
    (net (code "105") (name "unconnected-(D2D-PD4-Pad85)") (class "Default")
      (node (ref "D2") (pin "85") (pinfunction "PD4_85") (pintype "passive"))
    )
    (net (code "106") (name "unconnected-(D2D-PD5-Pad86)") (class "Default")
      (node (ref "D2") (pin "86") (pinfunction "PD5_86") (pintype "passive"))
    )
    (net (code "107") (name "unconnected-(D2D-PD6-Pad87)") (class "Default")
      (node (ref "D2") (pin "87") (pinfunction "PD6_87") (pintype "passive"))
    )
    (net (code "108") (name "unconnected-(D2D-PD7-Pad88)") (class "Default")
      (node (ref "D2") (pin "88") (pinfunction "PD7_88") (pintype "passive"))
    )
    (net (code "109") (name "unconnected-(D2D-PD10-Pad57)") (class "Default")
      (node (ref "D2") (pin "57") (pinfunction "PD10_57") (pintype "passive"))
    )
    (net (code "110") (name "unconnected-(D2D-PD12-Pad59)") (class "Default")
      (node (ref "D2") (pin "59") (pinfunction "PD12_59") (pintype "passive"))
    )
    (net (code "111") (name "unconnected-(D2D-PD14-Pad61)") (class "Default")
      (node (ref "D2") (pin "61") (pinfunction "PD14_61") (pintype "passive"))
    )
    (net (code "112") (name "unconnected-(D2D-PD15-Pad62)") (class "Default")
      (node (ref "D2") (pin "62") (pinfunction "PD15_62") (pintype "passive"))
    )
    (net (code "113") (name "unconnected-(D2E-PE0-Pad97)") (class "Default")
      (node (ref "D2") (pin "97") (pinfunction "PE0_97") (pintype "passive"))
    )
    (net (code "114") (name "unconnected-(D2E-PE1-Pad98)") (class "Default")
      (node (ref "D2") (pin "98") (pinfunction "PE1_98") (pintype "passive"))
    )
    (net (code "115") (name "unconnected-(D2E-PE2-Pad1)") (class "Default")
      (node (ref "D2") (pin "1") (pinfunction "PE2_1") (pintype "passive"))
    )
    (net (code "116") (name "unconnected-(D2E-PE3-Pad2)") (class "Default")
      (node (ref "D2") (pin "2") (pinfunction "PE3_2") (pintype "passive"))
    )
    (net (code "117") (name "unconnected-(D2E-PE4-Pad3)") (class "Default")
      (node (ref "D2") (pin "3") (pinfunction "PE4_3") (pintype "passive"))
    )
    (net (code "118") (name "unconnected-(D2E-PE5-Pad4)") (class "Default")
      (node (ref "D2") (pin "4") (pinfunction "PE5_4") (pintype "passive"))
    )
    (net (code "119") (name "unconnected-(D2E-PE6-Pad5)") (class "Default")
      (node (ref "D2") (pin "5") (pinfunction "PE6_5") (pintype "passive"))
    )
    (net (code "120") (name "unconnected-(D2E-PE7-Pad38)") (class "Default")
      (node (ref "D2") (pin "38") (pinfunction "PE7_38") (pintype "passive"))
    )
    (net (code "121") (name "unconnected-(D2E-PE8-Pad39)") (class "Default")
      (node (ref "D2") (pin "39") (pinfunction "PE8_39") (pintype "passive"))
    )
    (net (code "122") (name "unconnected-(D2E-PE9-Pad40)") (class "Default")
      (node (ref "D2") (pin "40") (pinfunction "PE9_40") (pintype "passive"))
    )
    (net (code "123") (name "unconnected-(D2E-PE10-Pad41)") (class "Default")
      (node (ref "D2") (pin "41") (pinfunction "PE10_41") (pintype "passive"))
    )
    (net (code "124") (name "unconnected-(D2E-PE11-Pad42)") (class "Default")
      (node (ref "D2") (pin "42") (pinfunction "PE11_42") (pintype "passive"))
    )
    (net (code "125") (name "unconnected-(D2E-PE12-Pad43)") (class "Default")
      (node (ref "D2") (pin "43") (pinfunction "PE12_43") (pintype "passive"))
    )
    (net (code "126") (name "unconnected-(D2E-PE13-Pad44)") (class "Default")
      (node (ref "D2") (pin "44") (pinfunction "PE13_44") (pintype "passive"))
    )
    (net (code "127") (name "unconnected-(D2E-PE14-Pad45)") (class "Default")
      (node (ref "D2") (pin "45") (pinfunction "PE14_45") (pintype "passive"))
    )
    (net (code "128") (name "unconnected-(D2E-PE15-Pad46)") (class "Default")
      (node (ref "D2") (pin "46") (pinfunction "PE15_46") (pintype "passive"))
    )
    (net (code "129") (name "unconnected-(D2F-VBAT-Pad6)") (class "Default")
      (node (ref "D2") (pin "6") (pinfunction "VBAT_6") (pintype "passive"))
    )
    (net (code "130") (name "unconnected-(D3-CTS#-Pad9)") (class "Default")
      (node (ref "D3") (pin "9") (pinfunction "CTS#_9") (pintype "passive"))
    )
    (net (code "131") (name "unconnected-(D3-DCD#-Pad12)") (class "Default")
      (node (ref "D3") (pin "12") (pinfunction "DCD#_12") (pintype "passive"))
    )
    (net (code "132") (name "unconnected-(D3-DSR#-Pad10)") (class "Default")
      (node (ref "D3") (pin "10") (pinfunction "DSR#_10") (pintype "passive"))
    )
    (net (code "133") (name "unconnected-(D3-DTR#-Pad13)") (class "Default")
      (node (ref "D3") (pin "13") (pinfunction "DTR#_13") (pintype "passive"))
    )
    (net (code "134") (name "unconnected-(D3-R232-Pad15)") (class "Default")
      (node (ref "D3") (pin "15") (pinfunction "R232_15") (pintype "passive"))
    )
    (net (code "135") (name "unconnected-(D3-RI#-Pad11)") (class "Default")
      (node (ref "D3") (pin "11") (pinfunction "RI#_11") (pintype "passive"))
    )
    (net (code "136") (name "unconnected-(D3-RTS#-Pad14)") (class "Default")
      (node (ref "D3") (pin "14") (pinfunction "RTS#_14") (pintype "passive"))
    )
    (net (code "137") (name "unconnected-(D3-V3-Pad4)") (class "Default")
      (node (ref "D3") (pin "4") (pinfunction "V3_4") (pintype "passive"))
    )
    (net (code "138") (name "unconnected-(D4-Remote-Pad3)") (class "Default")
      (node (ref "D4") (pin "3") (pinfunction "Remote_3") (pintype "passive"))
    )
    (net (code "139") (name "unconnected-(D4-–Vout-Pad8)") (class "Default")
      (node (ref "D4") (pin "8") (pinfunction "–Vout_8") (pintype "passive"))
    )
    (net (code "140") (name "unconnected-(D6-Remote-Pad3)") (class "Default")
      (node (ref "D6") (pin "3") (pinfunction "Remote_3") (pintype "passive"))
    )
    (net (code "141") (name "unconnected-(D6-–Vout-Pad8)") (class "Default")
      (node (ref "D6") (pin "8") (pinfunction "–Vout_8") (pintype "passive"))
    )
    (net (code "142") (name "unconnected-(X1-Pad11)") (class "Default")
      (node (ref "X1") (pin "11") (pinfunction "11_11") (pintype "passive"))
    )
    (net (code "143") (name "unconnected-(X1-Pad17)") (class "Default")
      (node (ref "X1") (pin "17") (pinfunction "17_17") (pintype "passive"))
    )
    (net (code "144") (name "unconnected-(X1-Pad19)") (class "Default")
      (node (ref "X1") (pin "19") (pinfunction "19_19") (pintype "passive"))
    )
    (net (code "145") (name "unconnected-(X7-Pad2)") (class "Default")
      (node (ref "X7") (pin "2") (pinfunction "2_2") (pintype "passive"))
    )
  )
)
